# Power_supplies.net
KiCad netlist of a schematic drawn in Altium Designer
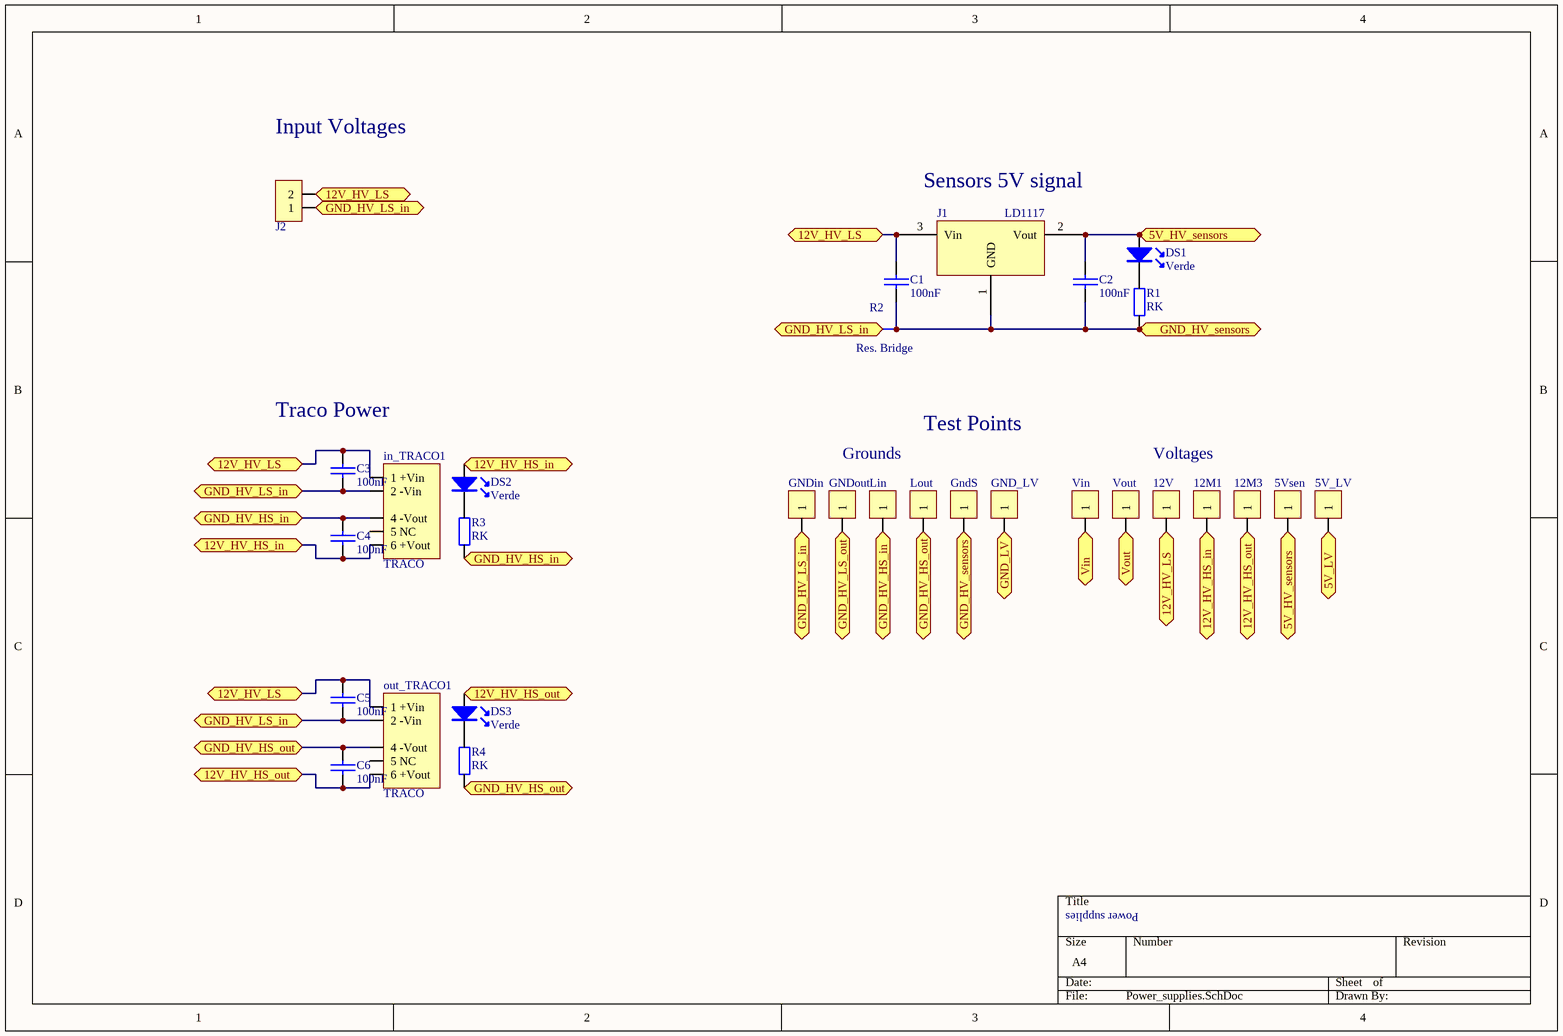
[diagram p0: Power_supplies.SchDoc]

(export (version "E")
  (design (tool "Eeschema 10.0.6"))
  (components
    (comp (ref "5Vsen")
      (value "Test Point")
      (footprint "Test_Point")
      (libsource (lib "SCH_Lib") (part "Test Point"))
    )
    (comp (ref "5V_LV")
      (value "Test Point")
      (footprint "Test_Point")
      (libsource (lib "SCH_Lib") (part "Test Point"))
    )
    (comp (ref "12M1")
      (value "Test Point")
      (footprint "Test_Point")
      (libsource (lib "SCH_Lib") (part "Test Point"))
    )
    (comp (ref "12M3")
      (value "Test Point")
      (footprint "Test_Point")
      (libsource (lib "SCH_Lib") (part "Test Point"))
    )
    (comp (ref "12V")
      (value "Test Point")
      (footprint "Test_Point")
      (libsource (lib "SCH_Lib") (part "Test Point"))
    )
    (comp (ref "C1")
      (value "100nF")
      (footprint "Cap100nF_AAU")
      (description "Condensador")
      (libsource (lib "SCH_Lib") (part "Condensador"))
    )
    (comp (ref "C2")
      (value "100nF")
      (footprint "Cap100nF_AAU")
      (description "Condensador")
      (libsource (lib "SCH_Lib") (part "Condensador"))
    )
    (comp (ref "C3")
      (value "100nF")
      (footprint "Cap100nF_AAU")
      (description "Condensador")
      (libsource (lib "SCH_Lib") (part "Condensador"))
    )
    (comp (ref "C4")
      (value "100nF")
      (footprint "Cap100nF_AAU")
      (description "Condensador")
      (libsource (lib "SCH_Lib") (part "Condensador"))
    )
    (comp (ref "C5")
      (value "100nF")
      (footprint "Cap100nF_AAU")
      (description "Condensador")
      (libsource (lib "SCH_Lib") (part "Condensador"))
    )
    (comp (ref "C6")
      (value "100nF")
      (footprint "Cap100nF_AAU")
      (description "Condensador")
      (libsource (lib "SCH_Lib") (part "Condensador"))
    )
    (comp (ref "DS1") (value "Verde") (footprint "Led 2mm") (libsource (lib "SCH_Lib") (part "Led")))
    (comp (ref "DS2") (value "Verde") (footprint "Led 2mm") (libsource (lib "SCH_Lib") (part "Led")))
    (comp (ref "DS3") (value "Verde") (footprint "Led 2mm") (libsource (lib "SCH_Lib") (part "Led")))
    (comp (ref "GNDin")
      (value "Test Point")
      (footprint "Test_Point")
      (libsource (lib "SCH_Lib") (part "Test Point"))
    )
    (comp (ref "GNDout")
      (value "Test Point")
      (footprint "Test_Point")
      (libsource (lib "SCH_Lib") (part "Test Point"))
    )
    (comp (ref "GndS")
      (value "Test Point")
      (footprint "Test_Point")
      (libsource (lib "SCH_Lib") (part "Test Point"))
    )
    (comp (ref "GND_LV")
      (value "Test Point")
      (footprint "Test_Point")
      (libsource (lib "SCH_Lib") (part "Test Point"))
    )
    (comp (ref "in_TRACO1")
      (value "TRACO")
      (footprint "TRACO_TMA1212S")
      (description "TracoPower TMA1212S")
      (libsource (lib "SCH_Lib") (part "TRACO"))
    )
    (comp (ref "J1")
      (value "LD1117")
      (footprint "SOT-223_LM1117")
      (description "Linear voltage regulator")
      (libsource (lib "SCH_Lib") (part "LD1117"))
    )
    (comp (ref "J2")
      (value "Cleva 2 vias")
      (footprint "Con2_Extron _3.5mmPitch")
      (libsource (lib "SCH_Lib") (part "Con_2"))
    )
    (comp (ref "Lin")
      (value "Test Point")
      (footprint "Test_Point")
      (libsource (lib "SCH_Lib") (part "Test Point"))
    )
    (comp (ref "Lout")
      (value "Test Point")
      (footprint "Test_Point")
      (libsource (lib "SCH_Lib") (part "Test Point"))
    )
    (comp (ref "out_TRACO1")
      (value "TRACO")
      (footprint "TRACO_TMA1212S")
      (description "TracoPower TMA1212S")
      (libsource (lib "SCH_Lib") (part "TRACO"))
    )
    (comp (ref "R1")
      (value "RK")
      (footprint "1206")
      (description "Resistencia")
      (libsource (lib "SCH_Lib") (part "Resistencia"))
    )
    (comp (ref "R2")
      (value "Res. Bridge")
      (footprint "1206")
      (description "Resistencia Bridge")
      (libsource (lib "SCH_Lib") (part "Res. Bridge"))
    )
    (comp (ref "R3")
      (value "RK")
      (footprint "1206")
      (description "Resistencia")
      (libsource (lib "SCH_Lib") (part "Resistencia"))
    )
    (comp (ref "R4")
      (value "RK")
      (footprint "1206")
      (description "Resistencia")
      (libsource (lib "SCH_Lib") (part "Resistencia"))
    )
    (comp (ref "Vin")
      (value "Test Point")
      (footprint "Test_Point")
      (libsource (lib "SCH_Lib") (part "Test Point"))
    )
    (comp (ref "Vout")
      (value "Test Point")
      (footprint "Test_Point")
      (libsource (lib "SCH_Lib") (part "Test Point"))
    )
  )
  (nets
    (net (code "1") (name "/5V_HV_sensors") (class "Default")
      (node (ref "5Vsen") (pin "1") (pinfunction "1_1") (pintype "passive"))
      (node (ref "C2") (pin "2") (pintype "passive"))
      (node (ref "DS1") (pin "A") (pinfunction "A_A") (pintype "passive"))
      (node (ref "J1") (pin "2") (pinfunction "Vout_2") (pintype "passive"))
    )
    (net (code "2") (name "/5V_LV") (class "Default")
      (node (ref "5V_LV") (pin "1") (pinfunction "1_1") (pintype "passive"))
    )
    (net (code "3") (name "/12V_HV_HS_in") (class "Default")
      (node (ref "12M1") (pin "1") (pinfunction "1_1") (pintype "passive"))
      (node (ref "C4") (pin "1") (pintype "passive"))
      (node (ref "DS2") (pin "A") (pinfunction "A_A") (pintype "passive"))
      (node (ref "in_TRACO1") (pin "6") (pinfunction "6_+Vout_6") (pintype "passive"))
    )
    (net (code "4") (name "/12V_HV_HS_out") (class "Default")
      (node (ref "12M3") (pin "1") (pinfunction "1_1") (pintype "passive"))
      (node (ref "C6") (pin "1") (pintype "passive"))
      (node (ref "DS3") (pin "A") (pinfunction "A_A") (pintype "passive"))
      (node (ref "out_TRACO1") (pin "6") (pinfunction "6_+Vout_6") (pintype "passive"))
    )
    (net (code "5") (name "/12V_HV_LS") (class "Default")
      (node (ref "12V") (pin "1") (pinfunction "1_1") (pintype "passive"))
      (node (ref "C1") (pin "2") (pintype "passive"))
      (node (ref "C3") (pin "2") (pintype "passive"))
      (node (ref "C5") (pin "2") (pintype "passive"))
      (node (ref "J1") (pin "3") (pinfunction "Vin_3") (pintype "passive"))
      (node (ref "J2") (pin "2") (pinfunction "2_2") (pintype "passive"))
      (node (ref "in_TRACO1") (pin "1") (pinfunction "1_+Vin_1") (pintype "passive"))
      (node (ref "out_TRACO1") (pin "1") (pinfunction "1_+Vin_1") (pintype "passive"))
    )
    (net (code "6") (name "/GND_HV_HS_in") (class "Default")
      (node (ref "C4") (pin "2") (pintype "passive"))
      (node (ref "Lin") (pin "1") (pinfunction "1_1") (pintype "passive"))
      (node (ref "R3") (pin "2") (pinfunction "2_2") (pintype "passive"))
      (node (ref "in_TRACO1") (pin "4") (pinfunction "4_-Vout_4") (pintype "passive"))
    )
    (net (code "7") (name "/GND_HV_HS_out") (class "Default")
      (node (ref "C6") (pin "2") (pintype "passive"))
      (node (ref "Lout") (pin "1") (pinfunction "1_1") (pintype "passive"))
      (node (ref "R4") (pin "2") (pinfunction "2_2") (pintype "passive"))
      (node (ref "out_TRACO1") (pin "4") (pinfunction "4_-Vout_4") (pintype "passive"))
    )
    (net (code "8") (name "/GND_HV_LS_in") (class "Default")
      (node (ref "C3") (pin "1") (pintype "passive"))
      (node (ref "C5") (pin "1") (pintype "passive"))
      (node (ref "GNDin") (pin "1") (pinfunction "1_1") (pintype "passive"))
      (node (ref "J2") (pin "1") (pinfunction "1_1") (pintype "passive"))
      (node (ref "R2") (pin "1") (pinfunction "1_1") (pintype "passive"))
      (node (ref "in_TRACO1") (pin "2") (pinfunction "2_-Vin_2") (pintype "passive"))
      (node (ref "out_TRACO1") (pin "2") (pinfunction "2_-Vin_2") (pintype "passive"))
    )
    (net (code "9") (name "/GND_HV_LS_out") (class "Default")
      (node (ref "GNDout") (pin "1") (pinfunction "1_1") (pintype "passive"))
    )
    (net (code "10") (name "/GND_HV_sensors") (class "Default")
      (node (ref "C1") (pin "1") (pintype "passive"))
      (node (ref "C2") (pin "1") (pintype "passive"))
      (node (ref "GndS") (pin "1") (pinfunction "1_1") (pintype "passive"))
      (node (ref "J1") (pin "1") (pinfunction "GND_1") (pintype "passive"))
      (node (ref "R1") (pin "2") (pinfunction "2_2") (pintype "passive"))
      (node (ref "R2") (pin "2") (pinfunction "2_2") (pintype "passive"))
    )
    (net (code "11") (name "/GND_LV") (class "Default")
      (node (ref "GND_LV") (pin "1") (pinfunction "1_1") (pintype "passive"))
    )
    (net (code "12") (name "/Vin") (class "Default")
      (node (ref "Vin") (pin "1") (pinfunction "1_1") (pintype "passive"))
    )
    (net (code "13") (name "/Vout") (class "Default")
      (node (ref "Vout") (pin "1") (pinfunction "1_1") (pintype "passive"))
    )
    (net (code "14") (name "Net-(DS1-PadK)") (class "Default")
      (node (ref "DS1") (pin "K") (pinfunction "K_K") (pintype "passive"))
      (node (ref "R1") (pin "1") (pinfunction "1_1") (pintype "passive"))
    )
    (net (code "15") (name "Net-(DS2-PadK)") (class "Default")
      (node (ref "DS2") (pin "K") (pinfunction "K_K") (pintype "passive"))
      (node (ref "R3") (pin "1") (pinfunction "1_1") (pintype "passive"))
    )
    (net (code "16") (name "Net-(DS3-PadK)") (class "Default")
      (node (ref "DS3") (pin "K") (pinfunction "K_K") (pintype "passive"))
      (node (ref "R4") (pin "1") (pinfunction "1_1") (pintype "passive"))
    )
    (net (code "17") (name "unconnected-(in_TRACO1-5_NC-Pad5)") (class "Default")
      (node (ref "in_TRACO1") (pin "5") (pinfunction "5_NC_5") (pintype "passive"))
    )
    (net (code "18") (name "unconnected-(out_TRACO1-5_NC-Pad5)") (class "Default")
      (node (ref "out_TRACO1") (pin "5") (pinfunction "5_NC_5") (pintype "passive"))
    )
  )
)
